# DSP_USB.net
KiCad netlist of a schematic drawn in Altium Designer
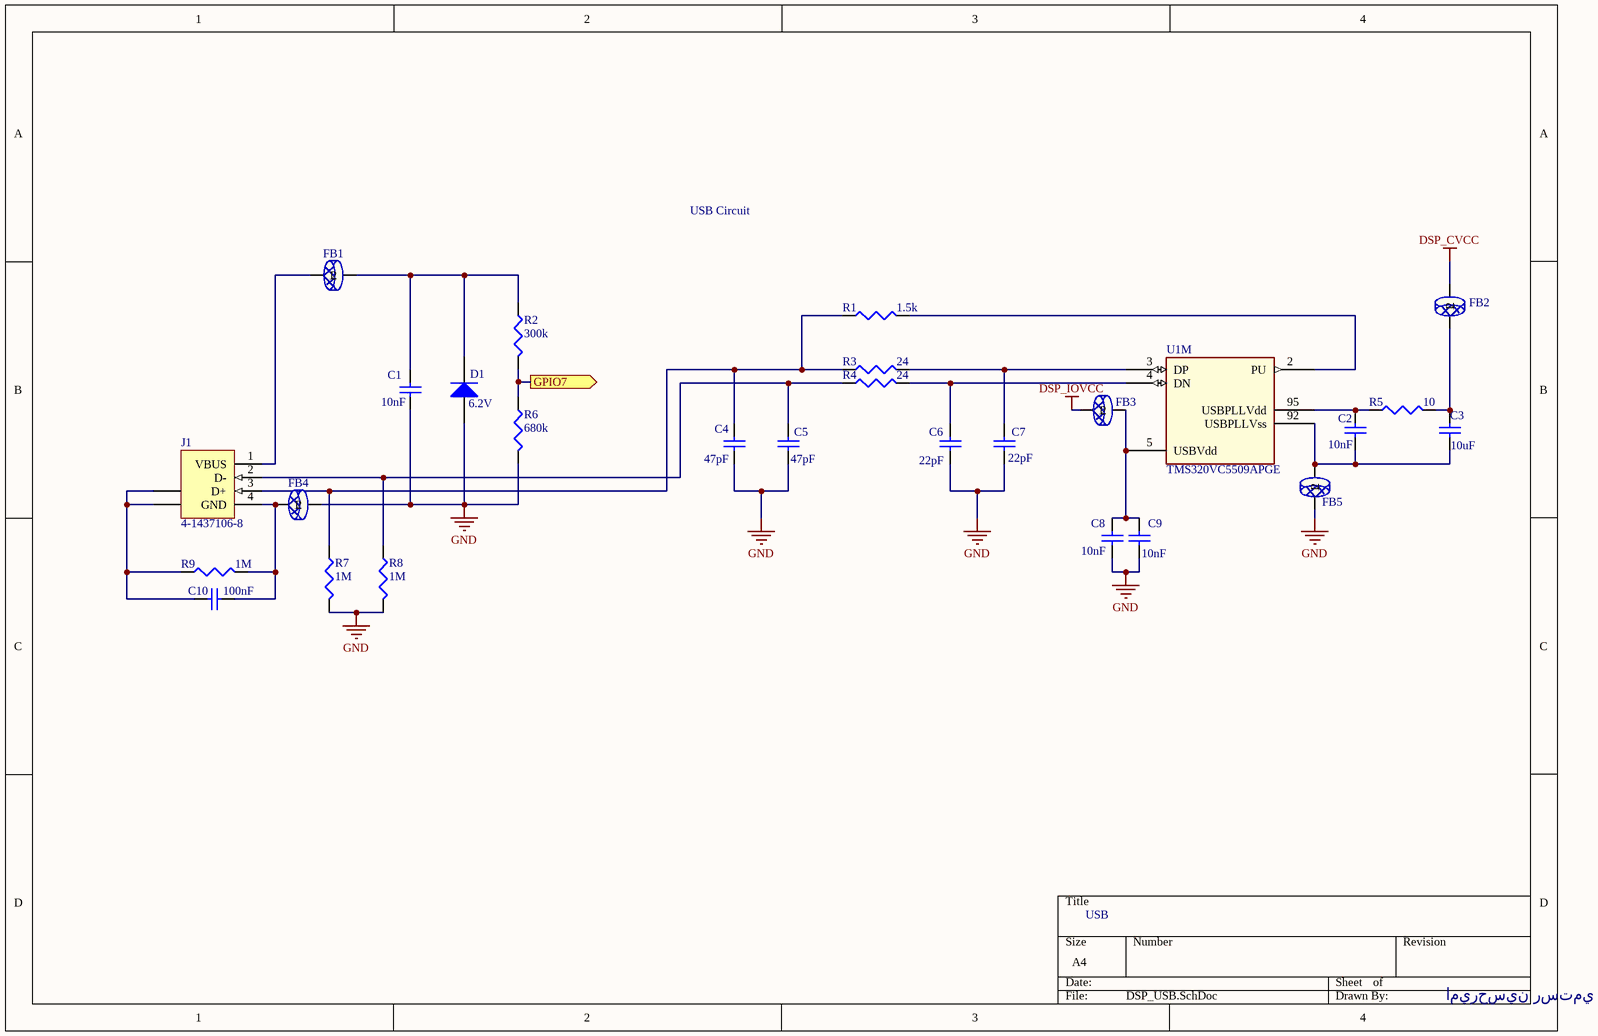
[diagram p0: DSP_USB.SchDoc]

(export (version "E")
  (design (tool "Eeschema 10.0.6"))
  (components
    (comp (ref "C1")
      (value "10nF")
      (footprint "1608[0603]")
      (description "Capacitor")
      (fields (field (name "PUBLISHER") "Altium Limited"))
      (libsource (lib "Miscellaneous Devices") (part "Cap Semi"))
    )
    (comp (ref "C2")
      (value "10nF")
      (footprint "1608[0603]")
      (description "Capacitor (Semiconductor SIM Model)")
      (fields (field (name "PUBLISHER") "Altium Limited"))
      (libsource (lib "Miscellaneous Devices") (part "Cap Semi"))
    )
    (comp (ref "C3")
      (value "10uF")
      (footprint "C1206")
      (description "Capacitor")
      (fields (field (name "PUBLISHER") "Altium Limited"))
      (libsource (lib "Miscellaneous Devices") (part "Cap Semi"))
    )
    (comp (ref "C4")
      (value "47pF")
      (footprint "1608[0603]")
      (description "Capacitor")
      (fields (field (name "PUBLISHER") "Altium Limited"))
      (libsource (lib "Miscellaneous Devices") (part "Cap Semi"))
    )
    (comp (ref "C5")
      (value "47pF")
      (footprint "1608[0603]")
      (description "Capacitor")
      (fields (field (name "PUBLISHER") "Altium Limited"))
      (libsource (lib "Miscellaneous Devices") (part "Cap Semi"))
    )
    (comp (ref "C6")
      (value "22pF")
      (footprint "1608[0603]")
      (description "Capacitor")
      (fields (field (name "PUBLISHER") "Altium Limited"))
      (libsource (lib "Miscellaneous Devices") (part "Cap Semi"))
    )
    (comp (ref "C7")
      (value "22pF")
      (footprint "1608[0603]")
      (description "Capacitor")
      (fields (field (name "Comment") "24pF") (field (name "PUBLISHER") "Altium Limited"))
      (libsource (lib "Miscellaneous Devices") (part "Cap Semi"))
    )
    (comp (ref "C8")
      (value "10nF")
      (footprint "1608[0603]")
      (description "Capacitor")
      (fields (field (name "PUBLISHER") "Altium Limited"))
      (libsource (lib "Miscellaneous Devices") (part "Cap Semi"))
    )
    (comp (ref "C9")
      (value "10nF")
      (footprint "1608[0603]")
      (description "Capacitor")
      (fields (field (name "PUBLISHER") "Altium Limited"))
      (libsource (lib "Miscellaneous Devices") (part "Cap Semi"))
    )
    (comp (ref "C10")
      (value "100nF")
      (footprint "1608[0603]")
      (description "Capacitor")
      (fields (field (name "PUBLISHER") "Altium Limited"))
      (libsource (lib "Miscellaneous Devices") (part "Cap Semi"))
    )
    (comp (ref "D1")
      (value "6.2V")
      (footprint "MELF-D3513-1405")
      (description "Diode zener")
      (fields (field (name "PUBLISHER") "Altium Limited"))
      (libsource (lib "Miscellaneous Devices") (part "Diode"))
    )
    (comp (ref "FB1")
      (value "50")
      (footprint "Miscellaneous Devices:3216[1206]")
      (description "Ferrite Bead")
      (libsource (lib "ferrite_bead") (part "Ferrite Bead"))
    )
    (comp (ref "FB2")
      (value "50")
      (footprint "Miscellaneous Devices:3216[1206]")
      (description "Ferrite Bead")
      (libsource (lib "") (part "Ferrite Bead_1"))
    )
    (comp (ref "FB3")
      (value "50")
      (footprint "Miscellaneous Devices:3216[1206]")
      (description "Ferrite Bead")
      (libsource (lib "ferrite_bead") (part "Ferrite Bead"))
    )
    (comp (ref "FB4")
      (value "50")
      (footprint "Miscellaneous Devices:3216[1206]")
      (description "Ferrite Bead")
      (libsource (lib "ferrite_bead") (part "Ferrite Bead"))
    )
    (comp (ref "FB5")
      (value "50")
      (footprint "Miscellaneous Devices:3216[1206]")
      (description "Ferrite Bead")
      (libsource (lib "") (part "Ferrite Bead_1"))
    )
    (comp (ref "J1")
      (value "4-1437106-8")
      (footprint "1437106")
      (description "USB 1.1, Right Angle, Thru-Hole, B Type, Receptacle, 4 Position, Natural")
      (fields (field (name "PUBLISHER") "Altium Limited"))
      (libsource (lib "AMP Serial Bus USB") (part "4-1437106-8"))
    )
    (comp (ref "R1")
      (value "1.5k")
      (footprint "J1-0603")
      (description "Resistor")
      (fields (field (name "PUBLISHER") "Altium Limited"))
      (libsource (lib "Miscellaneous Devices") (part "Res3"))
    )
    (comp (ref "R2")
      (value "300k")
      (footprint "J1-0603")
      (description "Resistor")
      (fields (field (name "PUBLISHER") "Altium Limited"))
      (libsource (lib "Miscellaneous Devices") (part "Res3"))
    )
    (comp (ref "R3")
      (value "24")
      (footprint "J1-0603")
      (description "Resistor")
      (fields (field (name "PUBLISHER") "Altium Limited"))
      (libsource (lib "Miscellaneous Devices") (part "Res3"))
    )
    (comp (ref "R4")
      (value "24")
      (footprint "J1-0603")
      (description "Resistor")
      (fields (field (name "PUBLISHER") "Altium Limited"))
      (libsource (lib "Miscellaneous Devices") (part "Res3"))
    )
    (comp (ref "R5")
      (value "10")
      (footprint "J1-0603")
      (description "Resistor")
      (fields (field (name "PUBLISHER") "Altium Limited"))
      (libsource (lib "Miscellaneous Devices") (part "Res3"))
    )
    (comp (ref "R6")
      (value "680k")
      (footprint "J1-0603")
      (description "Resistor")
      (fields (field (name "PUBLISHER") "Altium Limited"))
      (libsource (lib "Miscellaneous Devices") (part "Res3"))
    )
    (comp (ref "R7")
      (value "1M")
      (footprint "J1-0603")
      (description "Resistor")
      (fields (field (name "PUBLISHER") "Altium Limited"))
      (libsource (lib "Miscellaneous Devices") (part "Res3"))
    )
    (comp (ref "R8")
      (value "1M")
      (footprint "J1-0603")
      (description "Resistor")
      (fields (field (name "PUBLISHER") "Altium Limited"))
      (libsource (lib "Miscellaneous Devices") (part "Res3"))
    )
    (comp (ref "R9")
      (value "1M")
      (footprint "J1-0603")
      (description "Resistor")
      (fields (field (name "PUBLISHER") "Altium Limited"))
      (libsource (lib "Miscellaneous Devices") (part "Res3"))
    )
    (comp (ref "U1")
      (value "TMS320VC5509APGE")
      (footprint "TMSVC5509APGA")
      (libsource (lib "TMSVC5509APGE") (part "TMS320VC5509APGE"))
    )
  )
  (nets
    (net (code "1") (name "/GPIO7") (class "Default")
      (node (ref "R2") (pin "2") (pinfunction "2_2") (pintype "passive"))
      (node (ref "R6") (pin "1") (pinfunction "1_1") (pintype "passive"))
    )
    (net (code "2") (name "DSP_CVCC") (class "Default")
      (node (ref "FB2") (pin "1") (pinfunction "1_1") (pintype "passive"))
    )
    (net (code "3") (name "DSP_IOVCC") (class "Default")
      (node (ref "FB3") (pin "2") (pinfunction "2_2") (pintype "passive"))
    )
    (net (code "4") (name "GND") (class "Default")
      (node (ref "C1") (pin "2") (pinfunction "2_2") (pintype "passive"))
      (node (ref "C4") (pin "2") (pinfunction "2_2") (pintype "passive"))
      (node (ref "C5") (pin "2") (pinfunction "2_2") (pintype "passive"))
      (node (ref "C6") (pin "2") (pinfunction "2_2") (pintype "passive"))
      (node (ref "C7") (pin "2") (pinfunction "2_2") (pintype "passive"))
      (node (ref "C8") (pin "2") (pinfunction "2_2") (pintype "passive"))
      (node (ref "C9") (pin "2") (pinfunction "2_2") (pintype "passive"))
      (node (ref "D1") (pin "1") (pinfunction "A_1") (pintype "passive"))
      (node (ref "FB4") (pin "1") (pinfunction "1_1") (pintype "passive"))
      (node (ref "FB5") (pin "2") (pinfunction "2_2") (pintype "passive"))
      (node (ref "R6") (pin "2") (pinfunction "2_2") (pintype "passive"))
      (node (ref "R7") (pin "2") (pinfunction "2_2") (pintype "passive"))
      (node (ref "R8") (pin "2") (pinfunction "2_2") (pintype "passive"))
    )
    (net (code "5") (name "Net-(C3-Pad1)") (class "Default")
      (node (ref "C3") (pin "1") (pinfunction "1_1") (pintype "passive"))
      (node (ref "FB2") (pin "2") (pinfunction "2_2") (pintype "passive"))
      (node (ref "R5") (pin "2") (pinfunction "2_2") (pintype "passive"))
    )
    (net (code "6") (name "Net-(C10-Pad2)") (class "Default")
      (node (ref "C10") (pin "2") (pinfunction "2_2") (pintype "passive"))
      (node (ref "J1") (pin "5") (pinfunction "SHLD_5") (pintype "passive"))
      (node (ref "J1") (pin "6") (pinfunction "SHLD_6") (pintype "passive"))
      (node (ref "R9") (pin "1") (pinfunction "1_1") (pintype "passive"))
    )
    (net (code "7") (name "Net-(D1-K)") (class "Default")
      (node (ref "C1") (pin "1") (pinfunction "1_1") (pintype "passive"))
      (node (ref "D1") (pin "2") (pinfunction "K_2") (pintype "passive"))
      (node (ref "FB1") (pin "1") (pinfunction "1_1") (pintype "passive"))
      (node (ref "R2") (pin "1") (pinfunction "1_1") (pintype "passive"))
    )
    (net (code "8") (name "Net-(J1-D+)") (class "Default")
      (node (ref "C4") (pin "1") (pinfunction "1_1") (pintype "passive"))
      (node (ref "J1") (pin "3") (pinfunction "D+_3") (pintype "input"))
      (node (ref "R1") (pin "1") (pinfunction "1_1") (pintype "passive"))
      (node (ref "R3") (pin "1") (pinfunction "1_1") (pintype "passive"))
      (node (ref "R7") (pin "1") (pinfunction "1_1") (pintype "passive"))
    )
    (net (code "9") (name "Net-(J1-D-)") (class "Default")
      (node (ref "C5") (pin "1") (pinfunction "1_1") (pintype "passive"))
      (node (ref "J1") (pin "2") (pinfunction "D-_2") (pintype "input"))
      (node (ref "R4") (pin "1") (pinfunction "1_1") (pintype "passive"))
      (node (ref "R8") (pin "1") (pinfunction "1_1") (pintype "passive"))
    )
    (net (code "10") (name "Net-(J1-GND)") (class "Default")
      (node (ref "C10") (pin "1") (pinfunction "1_1") (pintype "passive"))
      (node (ref "FB4") (pin "2") (pinfunction "2_2") (pintype "passive"))
      (node (ref "J1") (pin "4") (pinfunction "GND_4") (pintype "power_in"))
      (node (ref "R9") (pin "2") (pinfunction "2_2") (pintype "passive"))
    )
    (net (code "11") (name "Net-(J1-VBUS)") (class "Default")
      (node (ref "FB1") (pin "2") (pinfunction "2_2") (pintype "passive"))
      (node (ref "J1") (pin "1") (pinfunction "VBUS_1") (pintype "power_in"))
    )
    (net (code "12") (name "Net-(U1M-DN)") (class "Default")
      (node (ref "C6") (pin "1") (pinfunction "1_1") (pintype "passive"))
      (node (ref "R4") (pin "2") (pinfunction "2_2") (pintype "passive"))
      (node (ref "U1") (pin "4") (pinfunction "DN_4") (pintype "bidirectional"))
    )
    (net (code "13") (name "Net-(U1M-DP)") (class "Default")
      (node (ref "C7") (pin "1") (pinfunction "1_1") (pintype "passive"))
      (node (ref "R3") (pin "2") (pinfunction "2_2") (pintype "passive"))
      (node (ref "U1") (pin "3") (pinfunction "DP_3") (pintype "bidirectional"))
    )
    (net (code "14") (name "Net-(U1M-PU)") (class "Default")
      (node (ref "R1") (pin "2") (pinfunction "2_2") (pintype "passive"))
      (node (ref "U1") (pin "2") (pinfunction "PU_2") (pintype "output"))
    )
    (net (code "15") (name "Net-(U1M-USBPLLVdd)") (class "Default")
      (node (ref "C2") (pin "1") (pinfunction "1_1") (pintype "passive"))
      (node (ref "R5") (pin "1") (pinfunction "1_1") (pintype "passive"))
      (node (ref "U1") (pin "95") (pinfunction "USBPLLVdd_95") (pintype "power_in"))
    )
    (net (code "16") (name "Net-(U1M-USBPLLVss)") (class "Default")
      (node (ref "C2") (pin "2") (pinfunction "2_2") (pintype "passive"))
      (node (ref "C3") (pin "2") (pinfunction "2_2") (pintype "passive"))
      (node (ref "FB5") (pin "1") (pinfunction "1_1") (pintype "passive"))
      (node (ref "U1") (pin "92") (pinfunction "USBPLLVss_92") (pintype "power_in"))
    )
    (net (code "17") (name "Net-(U1M-USBVdd)") (class "Default")
      (node (ref "C8") (pin "1") (pinfunction "1_1") (pintype "passive"))
      (node (ref "C9") (pin "1") (pinfunction "1_1") (pintype "passive"))
      (node (ref "FB3") (pin "1") (pinfunction "1_1") (pintype "passive"))
      (node (ref "U1") (pin "5") (pinfunction "USBVdd_5") (pintype "power_in"))
    )
  )
)
